# PROC051C_RST_LEDs.net
KiCad netlist of a schematic drawn in Altium Designer
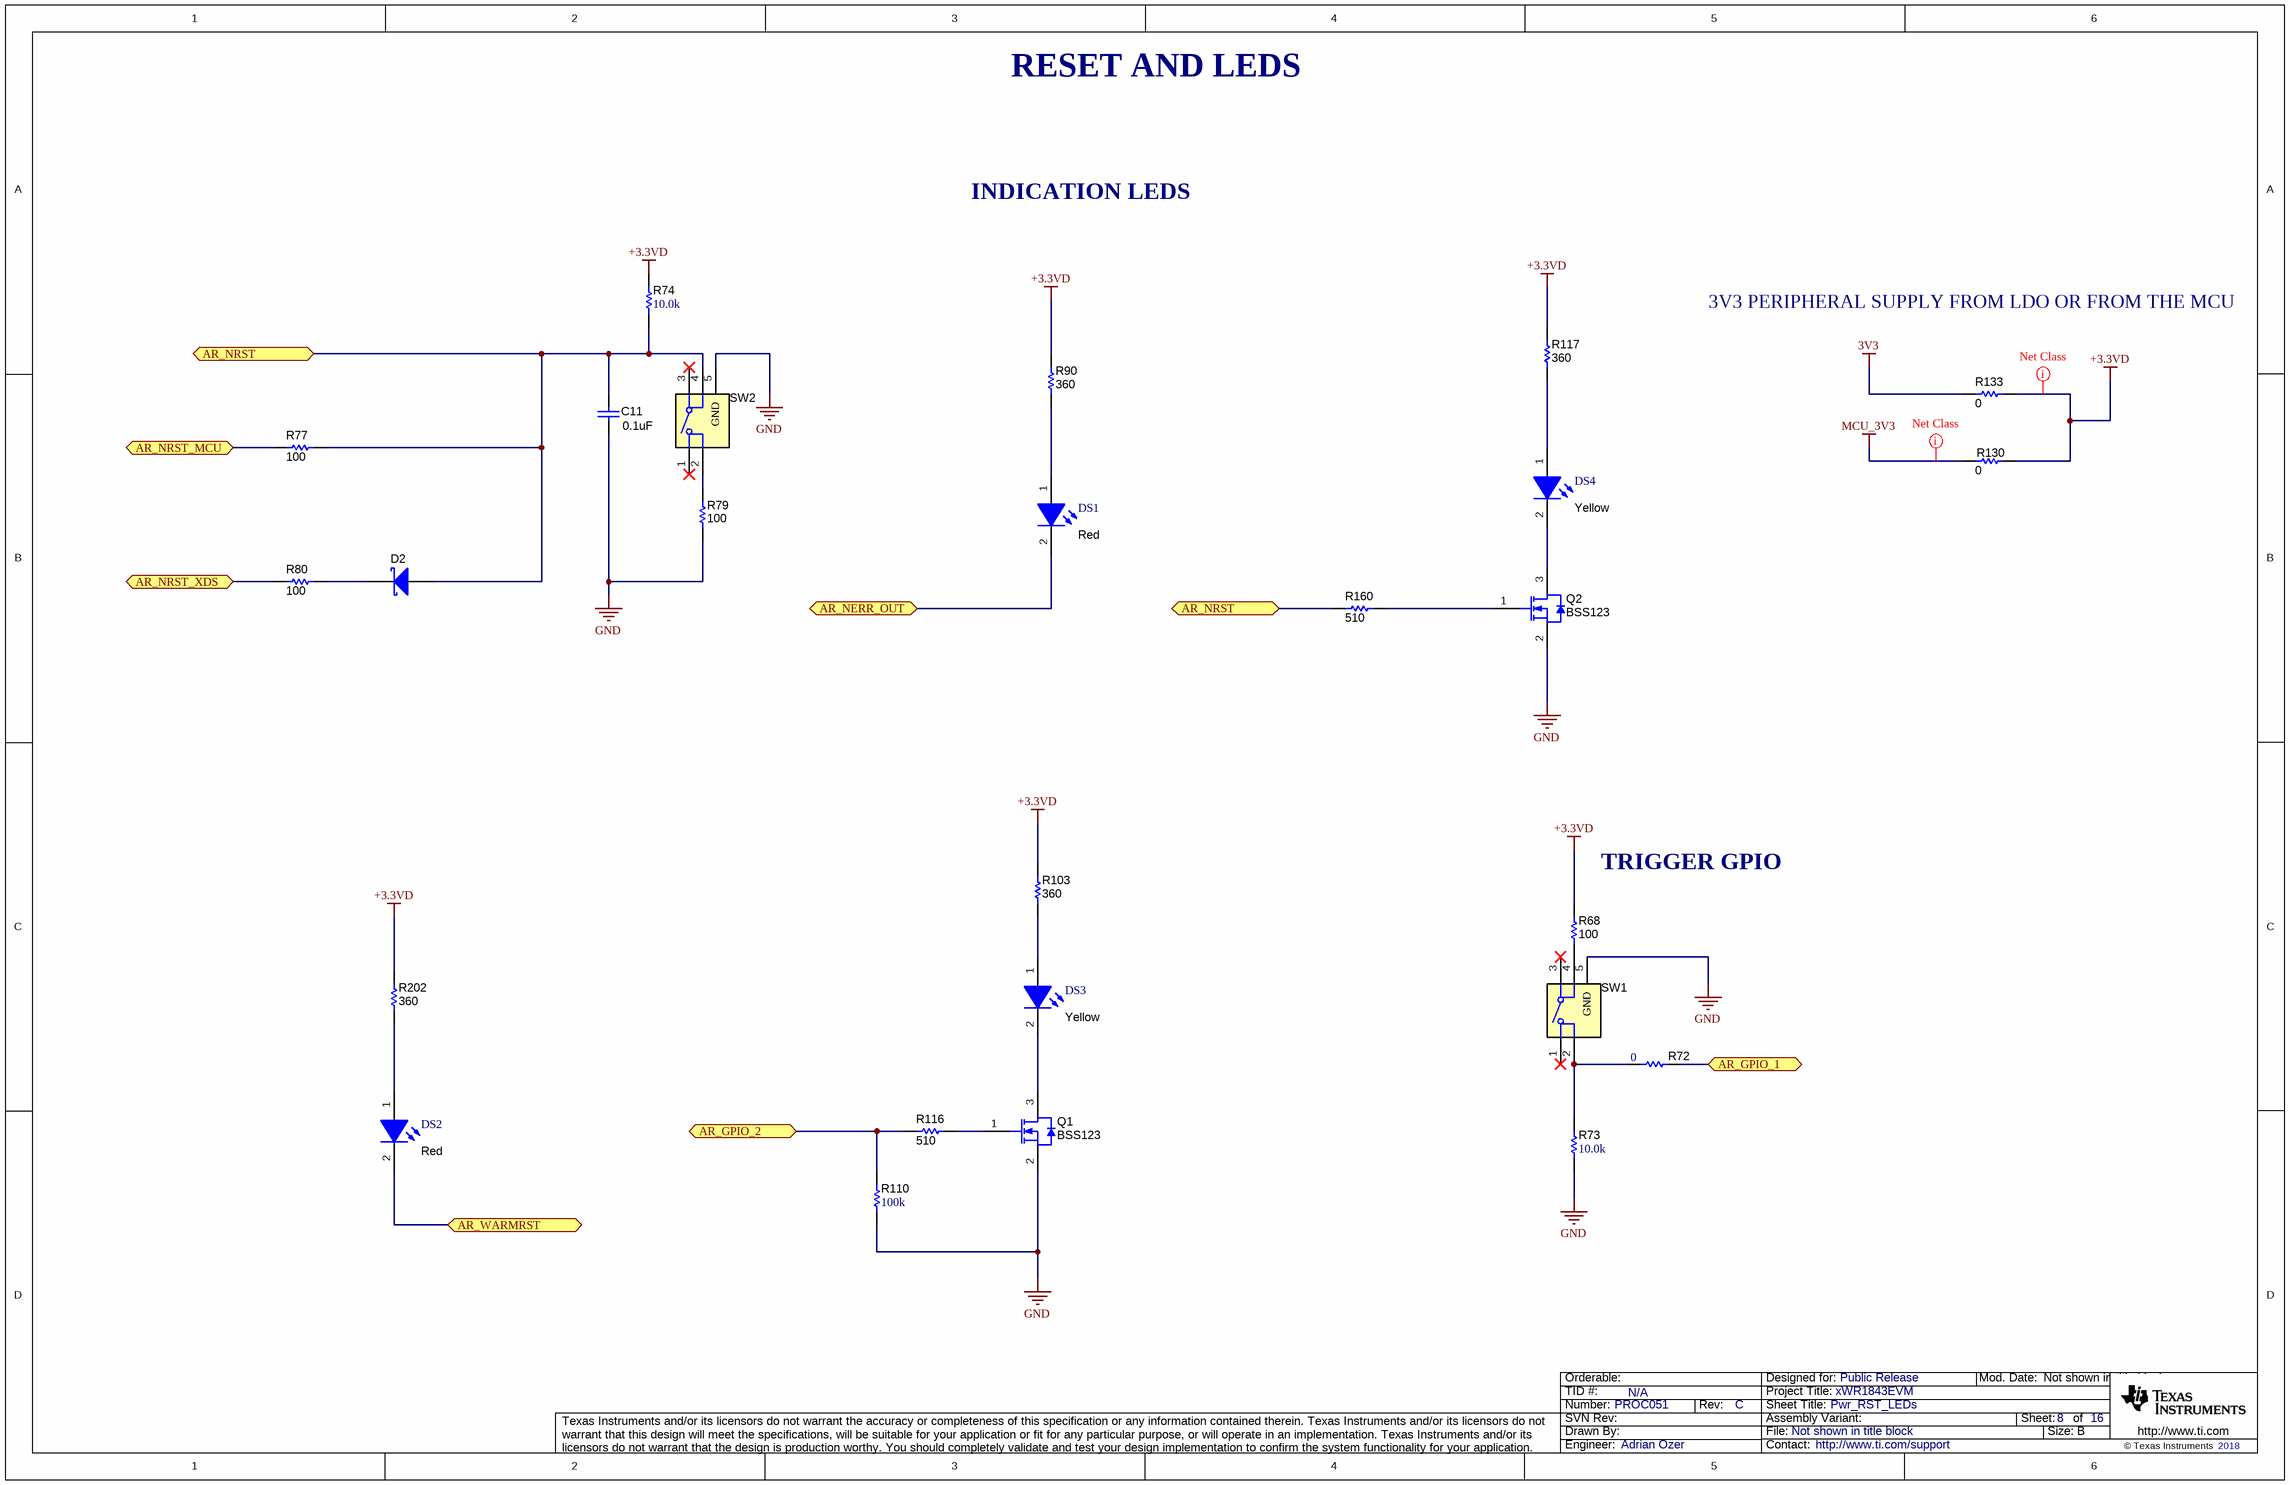
[diagram p0: PROC051C_RST_LEDs.SchDoc]

(export (version "E")
  (design (tool "Eeschema 10.0.6"))
  (components
    (comp (ref "C11")
      (value "GCM155R71C104KA55D")
      (footprint "0402L")
      (description "CAP, CERM, 0.1 uF, 16 V, +/- 10%, X7R, 0402")
      (fields
        (field (name "MANUFACTURER") "MuRata")
        (field (name "VALUEDISPLAYED") "0.1uF")
        (field (name "PUBLISHER") "Texas Instruments")
      )
      (libsource (lib "Altium Vault - TI") (part "Capacitor"))
    )
    (comp (ref "D2")
      (value "SMS3923-040LF")
      (footprint "SOD-882")
      (description "Diode, Schottky,  V, 0.01 A, SOD-882")
      (fields (field (name "MANUFACTURER") "Skyworks Solutions"))
      (libsource (lib "Altium Vault - TI") (part "DIODE_SCHOTTKY"))
    )
    (comp (ref "DS1")
      (value "Red")
      (footprint "LS L29K_Red")
      (description "LED, Red, SMD")
      (fields (field (name "MANUFACTURER") "OSRAM") (field (name "PARTNUMBER") "LS L29K-G1J2-1-Z"))
      (libsource (lib "Altium Vault - TI") (part "LED"))
    )
    (comp (ref "DS2")
      (value "Red")
      (footprint "LS L29K_Red")
      (description "LED, Red, SMD")
      (fields (field (name "MANUFACTURER") "OSRAM") (field (name "PARTNUMBER") "LS L29K-G1J2-1-Z"))
      (libsource (lib "Altium Vault - TI") (part "LED"))
    )
    (comp (ref "DS3")
      (value "Yellow")
      (footprint "SML-E1_Yellow")
      (description "LED, Yellow, SMD")
      (fields (field (name "MANUFACTURER") "Rohm") (field (name "PARTNUMBER") "SML-E12Y8WT86"))
      (libsource (lib "Altium Vault - TI") (part "LED"))
    )
    (comp (ref "DS4")
      (value "Yellow")
      (footprint "SML-E1_Yellow")
      (description "LED, Yellow, SMD")
      (fields (field (name "MANUFACTURER") "Rohm") (field (name "PARTNUMBER") "SML-E12Y8WT86"))
      (libsource (lib "Altium Vault - TI") (part "LED"))
    )
    (comp (ref "Q1")
      (value "BSS123")
      (footprint "SOT-23")
      (description "MOSFET, N-CH, 100 V, 0.17 A, SOT-23")
      (fields
        (field (name "MANUFACTURER") "Fairchild Semiconductor")
        (field (name "PUBLISHER") "Texas Instruments")
      )
      (libsource (lib "Altium Vault - TI") (part "MOSFET_N_D3G1S2"))
    )
    (comp (ref "Q2")
      (value "BSS123")
      (footprint "SOT-23")
      (description "MOSFET, N-CH, 100 V, 0.17 A, SOT-23")
      (fields
        (field (name "MANUFACTURER") "Fairchild Semiconductor")
        (field (name "PUBLISHER") "Texas Instruments")
      )
      (libsource (lib "Altium Vault - TI") (part "MOSFET_N_D3G1S2"))
    )
    (comp (ref "R68")
      (value "ERJ-2GEJ101X")
      (footprint "0402L")
      (description "RES, 100, 5%, 0.1 W, AEC-Q200 Grade 0, 0402")
      (fields
        (field (name "MANUFACTURER") "Panasonic")
        (field (name "VALUEDISPLAYED") "100")
        (field (name "PUBLISHER") "Texas Instruments")
      )
      (libsource (lib "Altium Vault - TI") (part "Resistor"))
    )
    (comp (ref "R72")
      (value "CRCW02010000Z0ED")
      (footprint "0201_Silk")
      (description "RES, 0, 5%, 0.05 W, 0201")
      (fields (field (name "MANUFACTURER") "Vishay-Dale") (field (name "VALUEDISPLAYED") "0"))
      (libsource (lib "Altium Vault - TI") (part "Resistor"))
    )
    (comp (ref "R73")
      (value "CRCW040210K0FKED")
      (footprint "0402L")
      (description "RES, 10.0 k, 1%, 0.063 W, AEC-Q200 Grade 0, 0402")
      (fields (field (name "MANUFACTURER") "Vishay-Dale") (field (name "VALUEDISPLAYED") "10.0k"))
      (libsource (lib "Altium Vault - TI") (part "Resistor"))
    )
    (comp (ref "R74")
      (value "CRCW040210K0FKED")
      (footprint "0402L")
      (description "RES, 10.0 k, 1%, 0.063 W, AEC-Q200 Grade 0, 0402")
      (fields (field (name "MANUFACTURER") "Vishay-Dale") (field (name "VALUEDISPLAYED") "10.0k"))
      (libsource (lib "Altium Vault - TI") (part "Resistor"))
    )
    (comp (ref "R77")
      (value "ERJ-2GEJ101X")
      (footprint "0402L")
      (description "RES, 100, 5%, 0.1 W, AEC-Q200 Grade 0, 0402")
      (fields
        (field (name "MANUFACTURER") "Panasonic")
        (field (name "VALUEDISPLAYED") "100")
        (field (name "PUBLISHER") "Texas Instruments")
      )
      (libsource (lib "Altium Vault - TI") (part "Resistor"))
    )
    (comp (ref "R79")
      (value "ERJ-2GEJ101X")
      (footprint "0402L")
      (description "RES, 100, 5%, 0.1 W, AEC-Q200 Grade 0, 0402")
      (fields
        (field (name "MANUFACTURER") "Panasonic")
        (field (name "VALUEDISPLAYED") "100")
        (field (name "PUBLISHER") "Texas Instruments")
      )
      (libsource (lib "Altium Vault - TI") (part "Resistor"))
    )
    (comp (ref "R80")
      (value "ERJ-2GEJ101X")
      (footprint "0402L")
      (description "RES, 100, 5%, 0.1 W, AEC-Q200 Grade 0, 0402")
      (fields
        (field (name "MANUFACTURER") "Panasonic")
        (field (name "VALUEDISPLAYED") "100")
        (field (name "PUBLISHER") "Texas Instruments")
      )
      (libsource (lib "Altium Vault - TI") (part "Resistor"))
    )
    (comp (ref "R90")
      (value "ERJ-2GEJ361X")
      (footprint "0402L")
      (description "RES, 360, 5%, 0.1 W, AEC-Q200 Grade 0, 0402")
      (fields (field (name "MANUFACTURER") "Panasonic") (field (name "VALUEDISPLAYED") "360"))
      (libsource (lib "Altium Vault - TI") (part "Resistor"))
    )
    (comp (ref "R103")
      (value "ERJ-2GEJ361X")
      (footprint "0402L")
      (description "RES, 360, 5%, 0.1 W, AEC-Q200 Grade 0, 0402")
      (fields (field (name "MANUFACTURER") "Panasonic") (field (name "VALUEDISPLAYED") "360"))
      (libsource (lib "Altium Vault - TI") (part "Resistor"))
    )
    (comp (ref "R110")
      (value "CRCW0402100KFKED")
      (footprint "0402L")
      (description "RES, 100 k, 1%, 0.063 W, AEC-Q200 Grade 0, 0402")
      (fields (field (name "MANUFACTURER") "Vishay-Dale") (field (name "VALUEDISPLAYED") "100k"))
      (libsource (lib "Altium Vault - TI") (part "Resistor"))
    )
    (comp (ref "R116")
      (value "ERJ-2GEJ511X")
      (footprint "0402L")
      (description "RES, 510, 5%, 0.1 W, AEC-Q200 Grade 0, 0402")
      (fields (field (name "MANUFACTURER") "Panasonic") (field (name "VALUEDISPLAYED") "510"))
      (libsource (lib "Altium Vault - TI") (part "Resistor"))
    )
    (comp (ref "R117")
      (value "ERJ-2GEJ361X")
      (footprint "0402L")
      (description "RES, 360, 5%, 0.1 W, AEC-Q200 Grade 0, 0402")
      (fields (field (name "MANUFACTURER") "Panasonic") (field (name "VALUEDISPLAYED") "360"))
      (libsource (lib "Altium Vault - TI") (part "Resistor"))
    )
    (comp (ref "R130")
      (value "MCT06030Z0000ZP500")
      (footprint "0603")
      (description "RES, 0, 5%, 0.125 W, 0603")
      (fields
        (field (name "MANUFACTURER") "Vishay/Beyschlag")
        (field (name "VALUEDISPLAYED") "0")
        (field (name "PUBLISHER") "Texas Instruments")
      )
      (libsource (lib "Altium Vault - TI") (part "CMP-0025884-3"))
    )
    (comp (ref "R133")
      (value "MCT06030Z0000ZP500")
      (footprint "0603")
      (description "RES, 0, 5%, 0.125 W, 0603")
      (fields
        (field (name "MANUFACTURER") "Vishay/Beyschlag")
        (field (name "VALUEDISPLAYED") "0")
        (field (name "PUBLISHER") "Texas Instruments")
      )
      (libsource (lib "Altium Vault - TI") (part "Resistor"))
    )
    (comp (ref "R160")
      (value "ERJ-2GEJ511X")
      (footprint "0402L")
      (description "RES, 510, 5%, 0.1 W, AEC-Q200 Grade 0, 0402")
      (fields (field (name "MANUFACTURER") "Panasonic") (field (name "VALUEDISPLAYED") "510"))
      (libsource (lib "Altium Vault - TI") (part "Resistor"))
    )
    (comp (ref "R202")
      (value "ERJ-2GEJ361X")
      (footprint "0402L")
      (description "RES, 360, 5%, 0.1 W, AEC-Q200 Grade 0, 0402")
      (fields (field (name "MANUFACTURER") "Panasonic") (field (name "VALUEDISPLAYED") "360"))
      (libsource (lib "Altium Vault - TI") (part "Resistor"))
    )
    (comp (ref "SW1")
      (value "KMR243GLFG")
      (footprint "SW_KMR243GLFG")
      (description "Switch, SPST-NO, Off-Mom, 0.01 A, 32 VDC, SMD")
      (fields (field (name "MANUFACTURER") "C&K Components") (field (name "PUBLISHER") "Texas Instruments"))
      (libsource (lib "Altium Vault - TI") (part "CMP-0002325-1"))
    )
    (comp (ref "SW2")
      (value "KMR243GLFG")
      (footprint "SW_KMR243GLFG")
      (description "Switch, SPST-NO, Off-Mom, 0.01 A, 32 VDC, SMD")
      (fields (field (name "MANUFACTURER") "C&K Components") (field (name "PUBLISHER") "Texas Instruments"))
      (libsource (lib "Altium Vault - TI") (part "CMP-0002325-1"))
    )
  )
  (nets
    (net (code "1") (name "+3.3VD") (class "Default")
      (node (ref "R103") (pin "2") (pinfunction "2_2") (pintype "passive"))
      (node (ref "R117") (pin "2") (pinfunction "2_2") (pintype "passive"))
      (node (ref "R130") (pin "2") (pinfunction "2_2") (pintype "passive"))
      (node (ref "R133") (pin "2") (pinfunction "2_2") (pintype "passive"))
      (node (ref "R202") (pin "2") (pinfunction "2_2") (pintype "passive"))
      (node (ref "R68") (pin "2") (pinfunction "2_2") (pintype "passive"))
      (node (ref "R74") (pin "2") (pinfunction "2_2") (pintype "passive"))
      (node (ref "R90") (pin "2") (pinfunction "2_2") (pintype "passive"))
    )
    (net (code "2") (name "/AR_GPIO_1") (class "Default")
      (node (ref "R72") (pin "2") (pinfunction "2_2") (pintype "passive"))
    )
    (net (code "3") (name "/AR_GPIO_2") (class "Default")
      (node (ref "R110") (pin "2") (pinfunction "2_2") (pintype "passive"))
      (node (ref "R116") (pin "1") (pinfunction "1_1") (pintype "passive"))
    )
    (net (code "4") (name "/AR_NERR_OUT") (class "Default")
      (node (ref "DS1") (pin "2") (pinfunction "K_2") (pintype "passive"))
    )
    (net (code "5") (name "/AR_NRST") (class "Default")
      (node (ref "C11") (pin "2") (pinfunction "2_2") (pintype "passive"))
      (node (ref "D2") (pin "2") (pinfunction "A_2") (pintype "passive"))
      (node (ref "R160") (pin "1") (pinfunction "1_1") (pintype "passive"))
      (node (ref "R74") (pin "1") (pinfunction "1_1") (pintype "passive"))
      (node (ref "R77") (pin "2") (pinfunction "2_2") (pintype "passive"))
      (node (ref "SW2") (pin "4") (pinfunction "4_4") (pintype "passive"))
    )
    (net (code "6") (name "/AR_NRST_MCU") (class "Default")
      (node (ref "R77") (pin "1") (pinfunction "1_1") (pintype "passive"))
    )
    (net (code "7") (name "/AR_NRST_XDS") (class "Default")
      (node (ref "R80") (pin "1") (pinfunction "1_1") (pintype "passive"))
    )
    (net (code "8") (name "/AR_WARMRST") (class "Default")
      (node (ref "DS2") (pin "2") (pinfunction "K_2") (pintype "passive"))
    )
    (net (code "9") (name "3V3") (class "Default")
      (node (ref "R133") (pin "1") (pinfunction "1_1") (pintype "passive"))
    )
    (net (code "10") (name "GND") (class "Default")
      (node (ref "C11") (pin "1") (pinfunction "1_1") (pintype "passive"))
      (node (ref "Q1") (pin "2") (pinfunction "S_2") (pintype "passive"))
      (node (ref "Q2") (pin "2") (pinfunction "S_2") (pintype "passive"))
      (node (ref "R110") (pin "1") (pinfunction "1_1") (pintype "passive"))
      (node (ref "R73") (pin "1") (pinfunction "1_1") (pintype "passive"))
      (node (ref "R79") (pin "1") (pinfunction "1_1") (pintype "passive"))
      (node (ref "SW1") (pin "5") (pinfunction "GND_5") (pintype "passive"))
      (node (ref "SW2") (pin "5") (pinfunction "GND_5") (pintype "passive"))
    )
    (net (code "11") (name "MCU_3V3") (class "Default")
      (node (ref "R130") (pin "1") (pinfunction "1_1") (pintype "passive"))
    )
    (net (code "12") (name "Net-(D2-K)") (class "Default")
      (node (ref "D2") (pin "1") (pinfunction "K_1") (pintype "passive"))
      (node (ref "R80") (pin "2") (pinfunction "2_2") (pintype "passive"))
    )
    (net (code "13") (name "Net-(DS1-A)") (class "Default")
      (node (ref "DS1") (pin "1") (pinfunction "A_1") (pintype "passive"))
      (node (ref "R90") (pin "1") (pinfunction "1_1") (pintype "passive"))
    )
    (net (code "14") (name "Net-(DS2-A)") (class "Default")
      (node (ref "DS2") (pin "1") (pinfunction "A_1") (pintype "passive"))
      (node (ref "R202") (pin "1") (pinfunction "1_1") (pintype "passive"))
    )
    (net (code "15") (name "Net-(DS3-A)") (class "Default")
      (node (ref "DS3") (pin "1") (pinfunction "A_1") (pintype "passive"))
      (node (ref "R103") (pin "1") (pinfunction "1_1") (pintype "passive"))
    )
    (net (code "16") (name "Net-(DS3-K)") (class "Default")
      (node (ref "DS3") (pin "2") (pinfunction "K_2") (pintype "passive"))
      (node (ref "Q1") (pin "3") (pinfunction "D_3") (pintype "passive"))
    )
    (net (code "17") (name "Net-(DS4-A)") (class "Default")
      (node (ref "DS4") (pin "1") (pinfunction "A_1") (pintype "passive"))
      (node (ref "R117") (pin "1") (pinfunction "1_1") (pintype "passive"))
    )
    (net (code "18") (name "Net-(DS4-K)") (class "Default")
      (node (ref "DS4") (pin "2") (pinfunction "K_2") (pintype "passive"))
      (node (ref "Q2") (pin "3") (pinfunction "D_3") (pintype "passive"))
    )
    (net (code "19") (name "Net-(Q1-G)") (class "Default")
      (node (ref "Q1") (pin "1") (pinfunction "G_1") (pintype "passive"))
      (node (ref "R116") (pin "2") (pinfunction "2_2") (pintype "passive"))
    )
    (net (code "20") (name "Net-(Q2-G)") (class "Default")
      (node (ref "Q2") (pin "1") (pinfunction "G_1") (pintype "passive"))
      (node (ref "R160") (pin "2") (pinfunction "2_2") (pintype "passive"))
    )
    (net (code "21") (name "Net-(R68-Pad1)") (class "Default")
      (node (ref "R68") (pin "1") (pinfunction "1_1") (pintype "passive"))
      (node (ref "SW1") (pin "4") (pinfunction "4_4") (pintype "passive"))
    )
    (net (code "22") (name "Net-(R72-Pad1)") (class "Default")
      (node (ref "R72") (pin "1") (pinfunction "1_1") (pintype "passive"))
      (node (ref "R73") (pin "2") (pinfunction "2_2") (pintype "passive"))
      (node (ref "SW1") (pin "2") (pinfunction "2_2") (pintype "passive"))
    )
    (net (code "23") (name "Net-(R79-Pad2)") (class "Default")
      (node (ref "R79") (pin "2") (pinfunction "2_2") (pintype "passive"))
      (node (ref "SW2") (pin "2") (pinfunction "2_2") (pintype "passive"))
    )
    (net (code "24") (name "unconnected-(SW1-Pad1)") (class "Default")
      (node (ref "SW1") (pin "1") (pinfunction "1_1") (pintype "passive+no_connect"))
    )
    (net (code "25") (name "unconnected-(SW1-Pad3)") (class "Default")
      (node (ref "SW1") (pin "3") (pinfunction "3_3") (pintype "passive+no_connect"))
    )
    (net (code "26") (name "unconnected-(SW2-Pad1)") (class "Default")
      (node (ref "SW2") (pin "1") (pinfunction "1_1") (pintype "passive+no_connect"))
    )
    (net (code "27") (name "unconnected-(SW2-Pad3)") (class "Default")
      (node (ref "SW2") (pin "3") (pinfunction "3_3") (pintype "passive+no_connect"))
    )
  )
)
